# Raspberry_Pi_CM4.net
KiCad netlist of a schematic drawn in Altium Designer
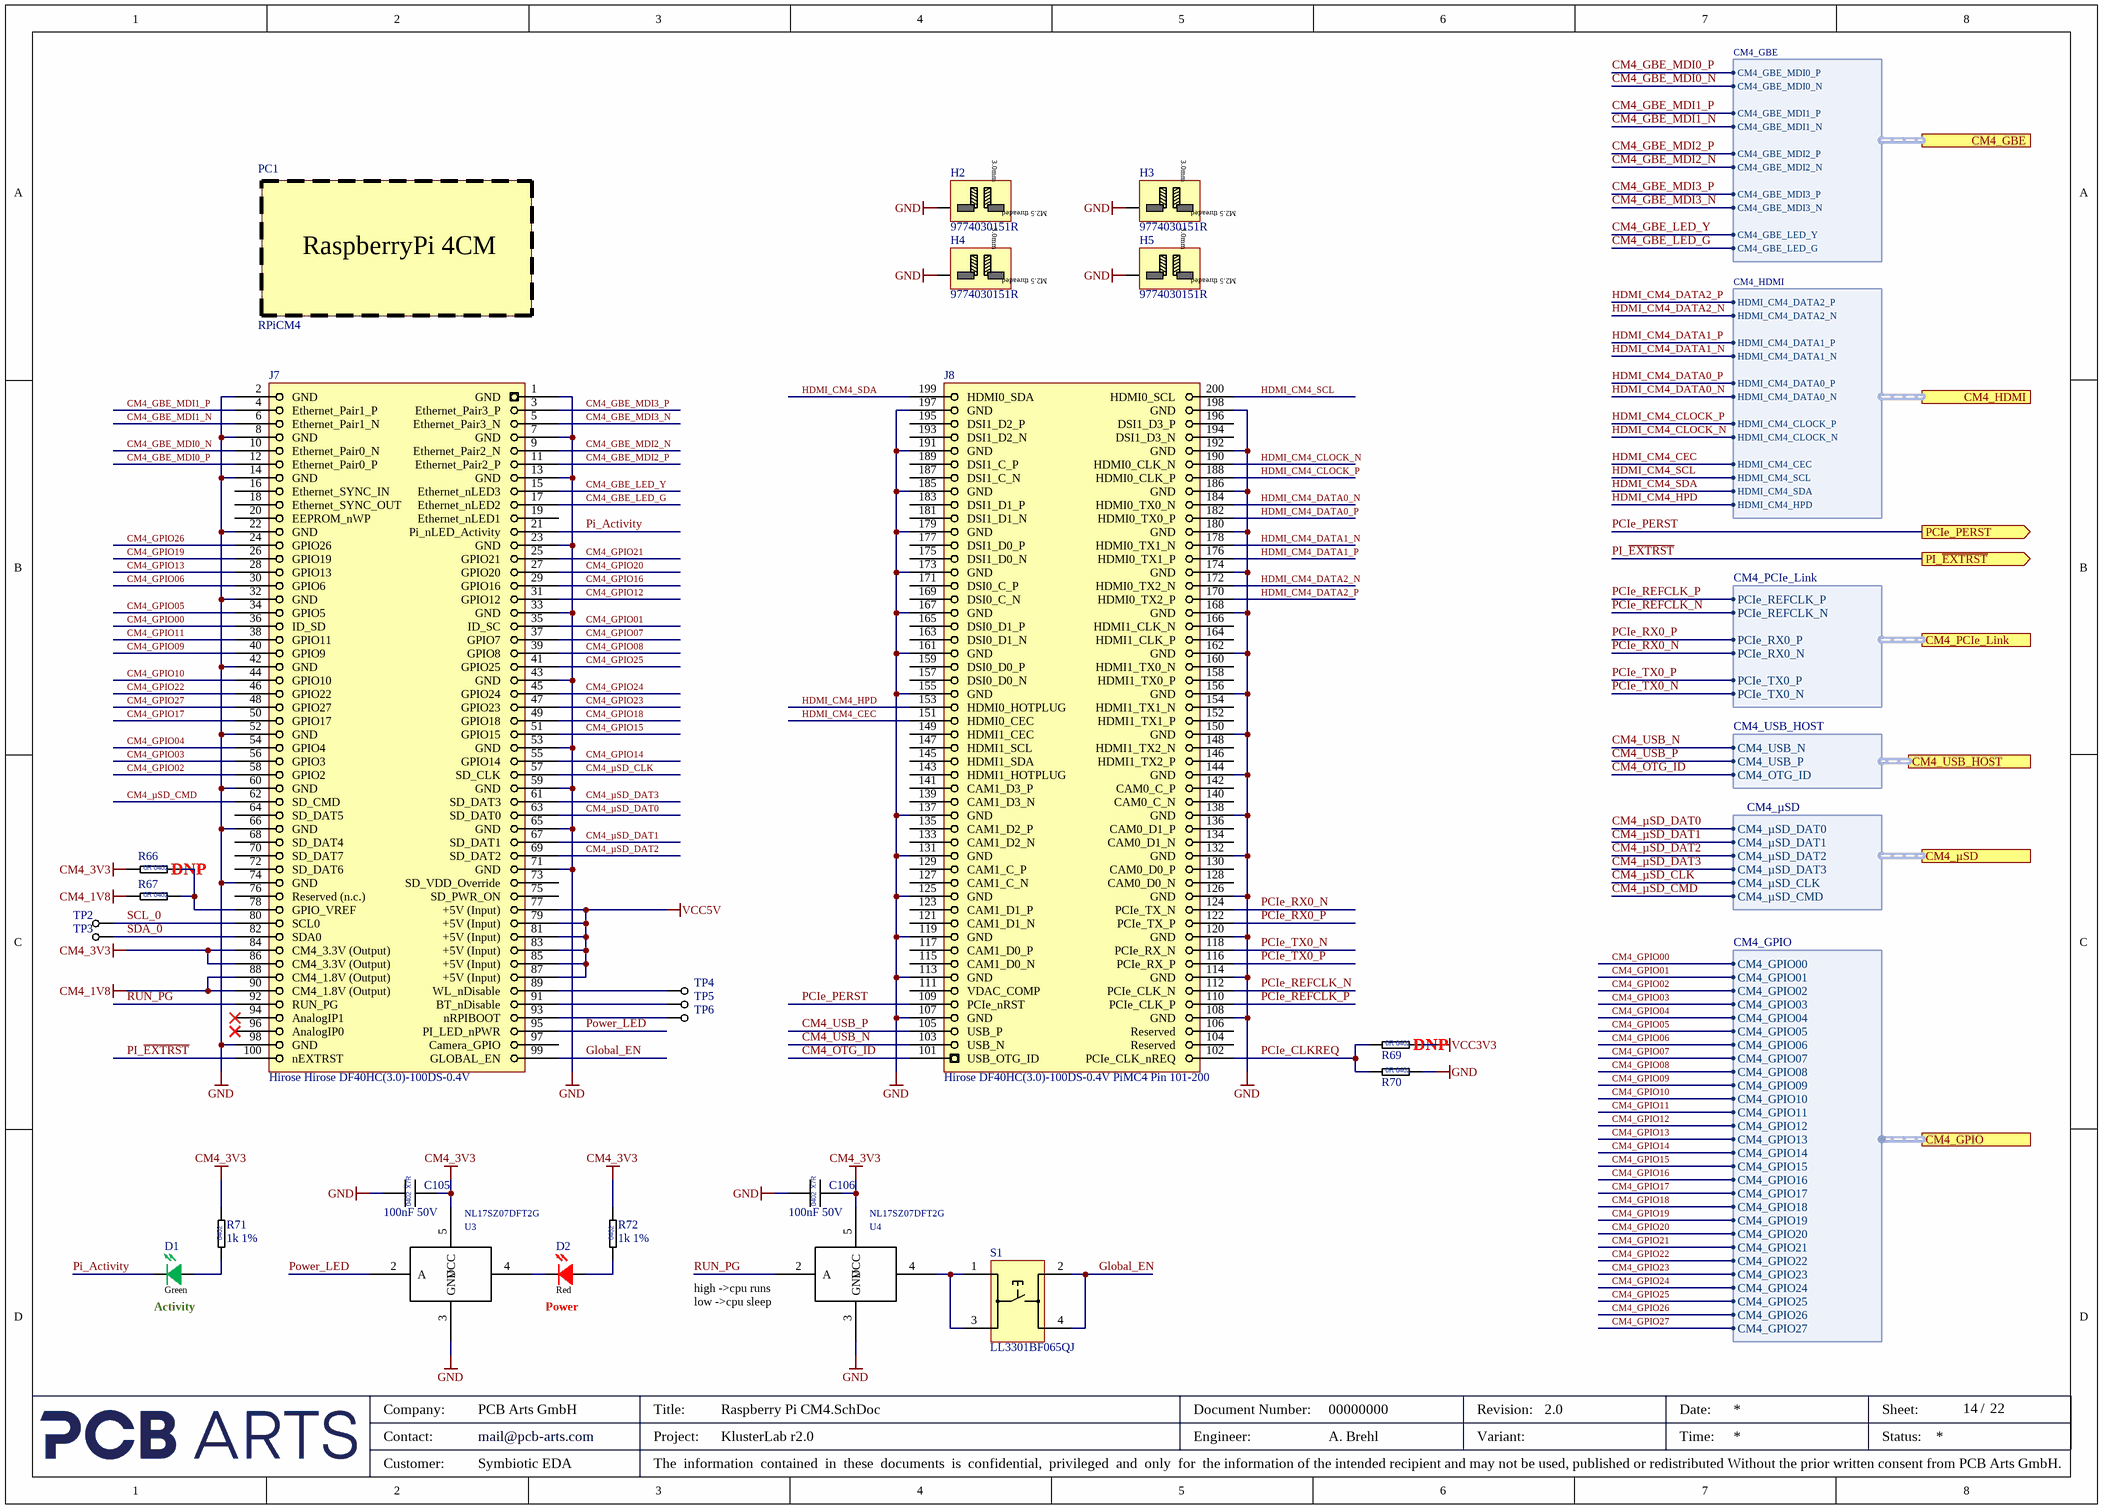
[diagram p0: Raspberry Pi CM4.SchDoc]

(export (version "E")
  (design (tool "Eeschema 10.0.6"))
  (components
    (comp (ref "C105")
      (value "100nF 50V")
      (footprint "Cap:CAP_0402_L")
      (description "Multilayer Ceramic Capacitors MLCC - SMD/SMT 0402 50VDC")
      (libsource (lib "Cap") (part "CAP_0402_100nF_50V"))
    )
    (comp (ref "C106")
      (value "100nF 50V")
      (footprint "Cap:CAP_0402_L")
      (description "Multilayer Ceramic Capacitors MLCC - SMD/SMT 0402 50VDC")
      (libsource (lib "Cap") (part "CAP_0402_100nF_50V"))
    )
    (comp (ref "D1")
      (value "LTST-S270KGKT")
      (footprint "Active:LED-0603 Sideview")
      (description "GREEN  0603 Light Emitting Diode")
      (fields (field (name "COLOR") "Green"))
      (libsource (lib "Active") (part "LED 0603 Green Sideview"))
    )
    (comp (ref "D2")
      (value "LTST-S270KRKT")
      (footprint "Active:LED-0603 Sideview")
      (description "RED  0603 Light Emitting Diode")
      (fields (field (name "COLOR") "Red"))
      (libsource (lib "Active") (part "LED 0603 Red Sideview"))
    )
    (comp (ref "H2")
      (value "9774030151R")
      (footprint "Electro_Mech:9774030151R")
      (description "Würth Standoff M2.5 h:3.0mm 9774030151R")
      (libsource (lib "Electro_Mech") (part "Würth Standoff M2.5 h{colon}3.0mm"))
    )
    (comp (ref "H3")
      (value "9774030151R")
      (footprint "Electro_Mech:9774030151R")
      (description "Würth Standoff M2.5 h:3.0mm 9774030151R")
      (libsource (lib "Electro_Mech") (part "Würth Standoff M2.5 h{colon}3.0mm"))
    )
    (comp (ref "H4")
      (value "9774030151R")
      (footprint "Electro_Mech:9774030151R")
      (description "Würth Standoff M2.5 h:3.0mm 9774030151R")
      (libsource (lib "Electro_Mech") (part "Würth Standoff M2.5 h{colon}3.0mm"))
    )
    (comp (ref "H5")
      (value "9774030151R")
      (footprint "Electro_Mech:9774030151R")
      (description "Würth Standoff M2.5 h:3.0mm 9774030151R")
      (libsource (lib "Electro_Mech") (part "Würth Standoff M2.5 h{colon}3.0mm"))
    )
    (comp (ref "J7")
      (value "Hirose Hirose DF40HC(3.0)-100DS-0.4V")
      (footprint "conn:Hirose DF40HC(3.0)-100DS-0.4V_1-100")
      (description "Hirose DF40HC(3.0)-100DS-0.4V 3mm heigth receptacle for Raspberry Pi CM4, Pin 1-100")
      (libsource (lib "Conn") (part "DF40HC(3.0)-100DS-0.4V RPiCM4 Pin 1-100"))
    )
    (comp (ref "J8")
      (value "Hirose DF40HC(3.0)-100DS-0.4V PiMC4 Pin 101-200")
      (footprint "Conn:Hirose DF40HC(3.0)-100DS-0.4V_101-200")
      (description "Hirose DF40C-100DS-0.4V 3mm heigth receptacle for Raspberry Pi CM4, Pin 101-200")
      (libsource (lib "Conn") (part "DF40HC(3.0)-100DS-0.4V RPiCM4 Pin 101-200"))
    )
    (comp (ref "PC1")
      (value "RPiCM4")
      (footprint "Mechanical:RaspberryPi_CM4")
      (description "Raspberry Pi 4 Compute Module 4")
      (libsource (lib "Mechanical") (part "Raspberry Pi Compute Module 4"))
    )
    (comp (ref "R66")
      (value "0R Jumper")
      (footprint "Res:RES_0402_L")
      (description "Thick Film Resistors - SMD 0Ohm")
      (libsource (lib "Res") (part "RES_0402_0R Jumper"))
    )
    (comp (ref "R67")
      (value "0R Jumper")
      (footprint "Res:RES_0402_L")
      (description "Thick Film Resistors - SMD 0Ohm")
      (libsource (lib "Res") (part "RES_0402_0R Jumper"))
    )
    (comp (ref "R69")
      (value "0R Jumper")
      (footprint "Res:RES_0402_L")
      (description "Thick Film Resistors - SMD 0Ohm")
      (libsource (lib "Res") (part "RES_0402_0R Jumper"))
    )
    (comp (ref "R70")
      (value "0R Jumper")
      (footprint "Res:RES_0402_L")
      (description "Thick Film Resistors - SMD 0Ohm")
      (libsource (lib "Res") (part "RES_0402_0R Jumper"))
    )
    (comp (ref "R71")
      (value "1k 1%")
      (footprint "Res:RES_0402_L")
      (description "Thick Film Resistors - SMD 1kOhm 1%")
      (libsource (lib "Res") (part "RES_0402_1k_1%"))
    )
    (comp (ref "R72")
      (value "1k 1%")
      (footprint "Res:RES_0402_L")
      (description "Thick Film Resistors - SMD 1kOhm 1%")
      (libsource (lib "Res") (part "RES_0402_1k_1%"))
    )
    (comp (ref "S1")
      (value "LL3301BF065QJ")
      (footprint "Electro_Mech:LL3301BF065QJ")
      (description "SPST Top Actuated  Button, 65gf, SMD h: 9.8mm")
      (libsource (lib "Electro_Mech") (part "LL3301BF065QJ_SPST Top Actuated  Button, 65gf, SMD h{colon} 9.8mm"))
    )
    (comp (ref "TP2")
      (value "Testpoint")
      (footprint "Electro_mech:Testpoint 0.8mm")
      (description "Testpoint 0.8mm")
      (libsource (lib "Electro_Mech") (part "Testpoint 0.8mm"))
    )
    (comp (ref "TP3")
      (value "Testpoint")
      (footprint "Electro_mech:Testpoint 0.8mm")
      (description "Testpoint 0.8mm")
      (libsource (lib "Electro_Mech") (part "Testpoint 0.8mm"))
    )
    (comp (ref "TP4")
      (value "Testpoint")
      (footprint "Electro_mech:Testpoint 0.8mm")
      (description "Testpoint 0.8mm")
      (libsource (lib "Electro_Mech") (part "Testpoint 0.8mm"))
    )
    (comp (ref "TP5")
      (value "Testpoint")
      (footprint "Electro_mech:Testpoint 0.8mm")
      (description "Testpoint 0.8mm")
      (libsource (lib "Electro_Mech") (part "Testpoint 0.8mm"))
    )
    (comp (ref "TP6")
      (value "Testpoint")
      (footprint "Electro_mech:Testpoint 0.8mm")
      (description "Testpoint 0.8mm")
      (libsource (lib "Electro_Mech") (part "Testpoint 0.8mm"))
    )
    (comp (ref "U3")
      (value "NL17SZ07DFT2G")
      (footprint "Digital:SOT65P210X110-5N")
      (description "Puffer u. Leitungstreiber 1.65-5.5V Single Non-Inverting")
      (libsource (lib "Digital") (part "NL17SZ07DFT2G_Buffer 1.65-5.5V Single Non-Inverting"))
    )
    (comp (ref "U4")
      (value "NL17SZ07DFT2G")
      (footprint "Digital:SOT65P210X110-5N")
      (description "Puffer u. Leitungstreiber 1.65-5.5V Single Non-Inverting")
      (libsource (lib "Digital") (part "NL17SZ07DFT2G_Buffer 1.65-5.5V Single Non-Inverting"))
    )
  )
  (nets
    (net (code "7") (name "/CM4_GBE_LED_G") (class "Default")
      (node (ref "J7") (pin "17") (pinfunction "Ethernet_nLED2_17") (pintype "passive"))
    )
    (net (code "8") (name "/CM4_GBE_LED_Y") (class "Default")
      (node (ref "J7") (pin "15") (pinfunction "Ethernet_nLED3_15") (pintype "passive"))
    )
    (net (code "9") (name "/CM4_GBE_MDI0_N") (class "Default")
      (node (ref "J7") (pin "10") (pinfunction "Ethernet_Pair0_N_10") (pintype "passive"))
    )
    (net (code "10") (name "/CM4_GBE_MDI0_P") (class "Default")
      (node (ref "J7") (pin "12") (pinfunction "Ethernet_Pair0_P_12") (pintype "passive"))
    )
    (net (code "11") (name "/CM4_GBE_MDI1_N") (class "Default")
      (node (ref "J7") (pin "6") (pinfunction "Ethernet_Pair1_N_6") (pintype "passive"))
    )
    (net (code "12") (name "/CM4_GBE_MDI1_P") (class "Default")
      (node (ref "J7") (pin "4") (pinfunction "Ethernet_Pair1_P_4") (pintype "passive"))
    )
    (net (code "13") (name "/CM4_GBE_MDI2_N") (class "Default")
      (node (ref "J7") (pin "9") (pinfunction "Ethernet_Pair2_N_9") (pintype "passive"))
    )
    (net (code "14") (name "/CM4_GBE_MDI2_P") (class "Default")
      (node (ref "J7") (pin "11") (pinfunction "Ethernet_Pair2_P_11") (pintype "passive"))
    )
    (net (code "15") (name "/CM4_GBE_MDI3_N") (class "Default")
      (node (ref "J7") (pin "5") (pinfunction "Ethernet_Pair3_N_5") (pintype "passive"))
    )
    (net (code "16") (name "/CM4_GBE_MDI3_P") (class "Default")
      (node (ref "J7") (pin "3") (pinfunction "Ethernet_Pair3_P_3") (pintype "passive"))
    )
    (net (code "17") (name "/CM4_GPIO00") (class "Default")
      (node (ref "J7") (pin "36") (pinfunction "ID_SD_36") (pintype "passive"))
    )
    (net (code "18") (name "/CM4_GPIO01") (class "Default")
      (node (ref "J7") (pin "35") (pinfunction "ID_SC_35") (pintype "passive"))
    )
    (net (code "19") (name "/CM4_GPIO02") (class "Default")
      (node (ref "J7") (pin "58") (pinfunction "GPIO2_58") (pintype "passive"))
    )
    (net (code "20") (name "/CM4_GPIO03") (class "Default")
      (node (ref "J7") (pin "56") (pinfunction "GPIO3_56") (pintype "passive"))
    )
    (net (code "21") (name "/CM4_GPIO04") (class "Default")
      (node (ref "J7") (pin "54") (pinfunction "GPIO4_54") (pintype "passive"))
    )
    (net (code "22") (name "/CM4_GPIO05") (class "Default")
      (node (ref "J7") (pin "34") (pinfunction "GPIO5_34") (pintype "passive"))
    )
    (net (code "23") (name "/CM4_GPIO06") (class "Default")
      (node (ref "J7") (pin "30") (pinfunction "GPIO6_30") (pintype "passive"))
    )
    (net (code "24") (name "/CM4_GPIO07") (class "Default")
      (node (ref "J7") (pin "37") (pinfunction "GPIO7_37") (pintype "passive"))
    )
    (net (code "25") (name "/CM4_GPIO08") (class "Default")
      (node (ref "J7") (pin "39") (pinfunction "GPIO8_39") (pintype "passive"))
    )
    (net (code "26") (name "/CM4_GPIO09") (class "Default")
      (node (ref "J7") (pin "40") (pinfunction "GPIO9_40") (pintype "passive"))
    )
    (net (code "27") (name "/CM4_GPIO10") (class "Default")
      (node (ref "J7") (pin "44") (pinfunction "GPIO10_44") (pintype "passive"))
    )
    (net (code "28") (name "/CM4_GPIO11") (class "Default")
      (node (ref "J7") (pin "38") (pinfunction "GPIO11_38") (pintype "passive"))
    )
    (net (code "29") (name "/CM4_GPIO12") (class "Default")
      (node (ref "J7") (pin "31") (pinfunction "GPIO12_31") (pintype "passive"))
    )
    (net (code "30") (name "/CM4_GPIO13") (class "Default")
      (node (ref "J7") (pin "28") (pinfunction "GPIO13_28") (pintype "passive"))
    )
    (net (code "31") (name "/CM4_GPIO14") (class "Default")
      (node (ref "J7") (pin "55") (pinfunction "GPIO14_55") (pintype "passive"))
    )
    (net (code "32") (name "/CM4_GPIO15") (class "Default")
      (node (ref "J7") (pin "51") (pinfunction "GPIO15_51") (pintype "passive"))
    )
    (net (code "33") (name "/CM4_GPIO16") (class "Default")
      (node (ref "J7") (pin "29") (pinfunction "GPIO16_29") (pintype "passive"))
    )
    (net (code "34") (name "/CM4_GPIO17") (class "Default")
      (node (ref "J7") (pin "50") (pinfunction "GPIO17_50") (pintype "passive"))
    )
    (net (code "35") (name "/CM4_GPIO18") (class "Default")
      (node (ref "J7") (pin "49") (pinfunction "GPIO18_49") (pintype "passive"))
    )
    (net (code "36") (name "/CM4_GPIO19") (class "Default")
      (node (ref "J7") (pin "26") (pinfunction "GPIO19_26") (pintype "passive"))
    )
    (net (code "37") (name "/CM4_GPIO20") (class "Default")
      (node (ref "J7") (pin "27") (pinfunction "GPIO20_27") (pintype "passive"))
    )
    (net (code "38") (name "/CM4_GPIO21") (class "Default")
      (node (ref "J7") (pin "25") (pinfunction "GPIO21_25") (pintype "passive"))
    )
    (net (code "39") (name "/CM4_GPIO22") (class "Default")
      (node (ref "J7") (pin "46") (pinfunction "GPIO22_46") (pintype "passive"))
    )
    (net (code "40") (name "/CM4_GPIO23") (class "Default")
      (node (ref "J7") (pin "47") (pinfunction "GPIO23_47") (pintype "passive"))
    )
    (net (code "41") (name "/CM4_GPIO24") (class "Default")
      (node (ref "J7") (pin "45") (pinfunction "GPIO24_45") (pintype "passive"))
    )
    (net (code "42") (name "/CM4_GPIO25") (class "Default")
      (node (ref "J7") (pin "41") (pinfunction "GPIO25_41") (pintype "passive"))
    )
    (net (code "43") (name "/CM4_GPIO26") (class "Default")
      (node (ref "J7") (pin "24") (pinfunction "GPIO26_24") (pintype "passive"))
    )
    (net (code "44") (name "/CM4_GPIO27") (class "Default")
      (node (ref "J7") (pin "48") (pinfunction "GPIO27_48") (pintype "passive"))
    )
    (net (code "45") (name "/CM4_OTG_ID") (class "Default")
      (node (ref "J8") (pin "101") (pinfunction "USB_OTG_ID_101") (pintype "passive"))
    )
    (net (code "46") (name "/CM4_USB_N") (class "Default")
      (node (ref "J8") (pin "103") (pinfunction "USB_N_103") (pintype "passive"))
    )
    (net (code "47") (name "/CM4_USB_P") (class "Default")
      (node (ref "J8") (pin "105") (pinfunction "USB_P_105") (pintype "passive"))
    )
    (net (code "48") (name "/CM4_µSD_CLK") (class "Default")
      (node (ref "J7") (pin "57") (pinfunction "SD_CLK_57") (pintype "passive"))
    )
    (net (code "49") (name "/CM4_µSD_CMD") (class "Default")
      (node (ref "J7") (pin "62") (pinfunction "SD_CMD_62") (pintype "passive"))
    )
    (net (code "50") (name "/CM4_µSD_DAT0") (class "Default")
      (node (ref "J7") (pin "63") (pinfunction "SD_DAT0_63") (pintype "passive"))
    )
    (net (code "51") (name "/CM4_µSD_DAT1") (class "Default")
      (node (ref "J7") (pin "67") (pinfunction "SD_DAT1_67") (pintype "passive"))
    )
    (net (code "52") (name "/CM4_µSD_DAT2") (class "Default")
      (node (ref "J7") (pin "69") (pinfunction "SD_DAT2_69") (pintype "passive"))
    )
    (net (code "53") (name "/CM4_µSD_DAT3") (class "Default")
      (node (ref "J7") (pin "61") (pinfunction "SD_DAT3_61") (pintype "passive"))
    )
    (net (code "54") (name "/Global_EN") (class "Default")
      (node (ref "J7") (pin "99") (pinfunction "GLOBAL_EN_99") (pintype "passive"))
      (node (ref "S1") (pin "2") (pinfunction "2_2") (pintype "passive"))
      (node (ref "S1") (pin "4") (pinfunction "4_4") (pintype "passive"))
    )
    (net (code "55") (name "/HDMI_CM4_CEC") (class "Default")
      (node (ref "J8") (pin "151") (pinfunction "HDMI0_CEC_151") (pintype "passive"))
    )
    (net (code "56") (name "/HDMI_CM4_CLOCK_N") (class "Default")
      (node (ref "J8") (pin "190") (pinfunction "HDMI0_CLK_N_190") (pintype "passive"))
    )
    (net (code "57") (name "/HDMI_CM4_CLOCK_P") (class "Default")
      (node (ref "J8") (pin "188") (pinfunction "HDMI0_CLK_P_188") (pintype "passive"))
    )
    (net (code "58") (name "/HDMI_CM4_DATA0_N") (class "Default")
      (node (ref "J8") (pin "184") (pinfunction "HDMI0_TX0_N_184") (pintype "passive"))
    )
    (net (code "59") (name "/HDMI_CM4_DATA0_P") (class "Default")
      (node (ref "J8") (pin "182") (pinfunction "HDMI0_TX0_P_182") (pintype "passive"))
    )
    (net (code "60") (name "/HDMI_CM4_DATA1_N") (class "Default")
      (node (ref "J8") (pin "178") (pinfunction "HDMI0_TX1_N_178") (pintype "passive"))
    )
    (net (code "61") (name "/HDMI_CM4_DATA1_P") (class "Default")
      (node (ref "J8") (pin "176") (pinfunction "HDMI0_TX1_P_176") (pintype "passive"))
    )
    (net (code "62") (name "/HDMI_CM4_DATA2_N") (class "Default")
      (node (ref "J8") (pin "172") (pinfunction "HDMI0_TX2_N_172") (pintype "passive"))
    )
    (net (code "63") (name "/HDMI_CM4_DATA2_P") (class "Default")
      (node (ref "J8") (pin "170") (pinfunction "HDMI0_TX2_P_170") (pintype "passive"))
    )
    (net (code "64") (name "/HDMI_CM4_HPD") (class "Default")
      (node (ref "J8") (pin "153") (pinfunction "HDMI0_HOTPLUG_153") (pintype "passive"))
    )
    (net (code "65") (name "/HDMI_CM4_SCL") (class "Default")
      (node (ref "J8") (pin "200") (pinfunction "HDMI0_SCL_200") (pintype "passive"))
    )
    (net (code "66") (name "/HDMI_CM4_SDA") (class "Default")
      (node (ref "J8") (pin "199") (pinfunction "HDMI0_SDA_199") (pintype "passive"))
    )
    (net (code "67") (name "/PCIe_CLKREQ") (class "Default")
      (node (ref "J8") (pin "102") (pinfunction "PCIe_CLK_nREQ_102") (pintype "passive"))
      (node (ref "R69") (pin "1") (pinfunction "1_1") (pintype "passive"))
      (node (ref "R70") (pin "1") (pinfunction "1_1") (pintype "passive"))
    )
    (net (code "68") (name "/PCIe_PERST") (class "Default")
      (node (ref "J8") (pin "109") (pinfunction "PCIe_nRST_109") (pintype "passive"))
    )
    (net (code "69") (name "/PCIe_REFCLK_N") (class "Default")
      (node (ref "J8") (pin "112") (pinfunction "PCIe_CLK_N_112") (pintype "passive"))
    )
    (net (code "70") (name "/PCIe_REFCLK_P") (class "Default")
      (node (ref "J8") (pin "110") (pinfunction "PCIe_CLK_P_110") (pintype "passive"))
    )
    (net (code "71") (name "/PCIe_RX0_N") (class "Default")
      (node (ref "J8") (pin "124") (pinfunction "PCIe_TX_N_124") (pintype "passive"))
    )
    (net (code "72") (name "/PCIe_RX0_P") (class "Default")
      (node (ref "J8") (pin "122") (pinfunction "PCIe_TX_P_122") (pintype "passive"))
    )
    (net (code "73") (name "/PCIe_TX0_N") (class "Default")
      (node (ref "J8") (pin "118") (pinfunction "PCIe_RX_N_118") (pintype "passive"))
    )
    (net (code "74") (name "/PCIe_TX0_P") (class "Default")
      (node (ref "J8") (pin "116") (pinfunction "PCIe_RX_P_116") (pintype "passive"))
    )
    (net (code "75") (name "/PI_~{EXTRST}") (class "Default")
      (node (ref "J7") (pin "100") (pinfunction "nEXTRST_100") (pintype "passive"))
    )
    (net (code "76") (name "/Pi_Activity") (class "Default")
      (node (ref "D1") (pin "1") (pinfunction "1_1") (pintype "passive"))
      (node (ref "J7") (pin "21") (pinfunction "Pi_nLED_Activity_21") (pintype "passive"))
    )
    (net (code "77") (name "/Power_LED") (class "Default")
      (node (ref "J7") (pin "95") (pinfunction "PI_LED_nPWR_95") (pintype "passive"))
      (node (ref "U3") (pin "2") (pinfunction "A_2") (pintype "passive"))
    )
    (net (code "78") (name "/RUN_PG") (class "Default")
      (node (ref "J7") (pin "92") (pinfunction "RUN_PG_92") (pintype "passive"))
      (node (ref "U4") (pin "2") (pinfunction "A_2") (pintype "passive"))
    )
    (net (code "79") (name "/SCL_0") (class "Default")
      (node (ref "J7") (pin "80") (pinfunction "SCL0_80") (pintype "passive"))
      (node (ref "TP2") (pin "1") (pinfunction "GND_1") (pintype "passive"))
    )
    (net (code "80") (name "/SDA_0") (class "Default")
      (node (ref "J7") (pin "82") (pinfunction "SDA0_82") (pintype "passive"))
      (node (ref "TP3") (pin "1") (pinfunction "GND_1") (pintype "passive"))
    )
    (net (code "87") (name "CM4_1V8") (class "Default")
      (node (ref "J7") (pin "88") (pinfunction "CM4_1.8V_(Output)_88") (pintype "passive"))
      (node (ref "J7") (pin "90") (pinfunction "CM4_1.8V_(Output)_90") (pintype "passive"))
      (node (ref "R67") (pin "1") (pinfunction "1_1") (pintype "passive"))
    )
    (net (code "88") (name "CM4_3V3") (class "Default")
      (node (ref "C105") (pin "2") (pinfunction "2_2") (pintype "passive"))
      (node (ref "C106") (pin "2") (pinfunction "2_2") (pintype "passive"))
      (node (ref "J7") (pin "84") (pinfunction "CM4_3.3V_(Output)_84") (pintype "passive"))
      (node (ref "J7") (pin "86") (pinfunction "CM4_3.3V_(Output)_86") (pintype "passive"))
      (node (ref "R66") (pin "1") (pinfunction "1_1") (pintype "passive"))
      (node (ref "R71") (pin "2") (pinfunction "2_2") (pintype "passive"))
      (node (ref "R72") (pin "2") (pinfunction "2_2") (pintype "passive"))
      (node (ref "U3") (pin "5") (pinfunction "VCC_5") (pintype "passive"))
      (node (ref "U4") (pin "5") (pinfunction "VCC_5") (pintype "passive"))
    )
    (net (code "89") (name "GND") (class "Default")
      (node (ref "C105") (pin "1") (pinfunction "1_1") (pintype "passive"))
      (node (ref "C106") (pin "1") (pinfunction "1_1") (pintype "passive"))
      (node (ref "H2") (pin "1") (pinfunction "1_1") (pintype "passive"))
      (node (ref "H3") (pin "1") (pinfunction "1_1") (pintype "passive"))
      (node (ref "H4") (pin "1") (pinfunction "1_1") (pintype "passive"))
      (node (ref "H5") (pin "1") (pinfunction "1_1") (pintype "passive"))
      (node (ref "J7") (pin "1") (pinfunction "GND_1") (pintype "passive"))
      (node (ref "J7") (pin "13") (pinfunction "GND_13") (pintype "passive"))
      (node (ref "J7") (pin "14") (pinfunction "GND_14") (pintype "passive"))
      (node (ref "J7") (pin "2") (pinfunction "GND_2") (pintype "passive"))
      (node (ref "J7") (pin "22") (pinfunction "GND_22") (pintype "passive"))
      (node (ref "J7") (pin "23") (pinfunction "GND_23") (pintype "passive"))
      (node (ref "J7") (pin "32") (pinfunction "GND_32") (pintype "passive"))
      (node (ref "J7") (pin "33") (pinfunction "GND_33") (pintype "passive"))
      (node (ref "J7") (pin "42") (pinfunction "GND_42") (pintype "passive"))
      (node (ref "J7") (pin "43") (pinfunction "GND_43") (pintype "passive"))
      (node (ref "J7") (pin "52") (pinfunction "GND_52") (pintype "passive"))
      (node (ref "J7") (pin "53") (pinfunction "GND_53") (pintype "passive"))
      (node (ref "J7") (pin "59") (pinfunction "GND_59") (pintype "passive"))
      (node (ref "J7") (pin "60") (pinfunction "GND_60") (pintype "passive"))
      (node (ref "J7") (pin "65") (pinfunction "GND_65") (pintype "passive"))
      (node (ref "J7") (pin "66") (pinfunction "GND_66") (pintype "passive"))
      (node (ref "J7") (pin "7") (pinfunction "GND_7") (pintype "passive"))
      (node (ref "J7") (pin "71") (pinfunction "GND_71") (pintype "passive"))
      (node (ref "J7") (pin "74") (pinfunction "GND_74") (pintype "passive"))
      (node (ref "J7") (pin "8") (pinfunction "GND_8") (pintype "passive"))
      (node (ref "J7") (pin "98") (pinfunction "GND_98") (pintype "passive"))
      (node (ref "J8") (pin "107") (pinfunction "GND_107") (pintype "passive"))
      (node (ref "J8") (pin "108") (pinfunction "GND_108") (pintype "passive"))
      (node (ref "J8") (pin "113") (pinfunction "GND_113") (pintype "passive"))
      (node (ref "J8") (pin "114") (pinfunction "GND_114") (pintype "passive"))
      (node (ref "J8") (pin "119") (pinfunction "GND_119") (pintype "passive"))
      (node (ref "J8") (pin "120") (pinfunction "GND_120") (pintype "passive"))
      (node (ref "J8") (pin "125") (pinfunction "GND_125") (pintype "passive"))
      (node (ref "J8") (pin "126") (pinfunction "GND_126") (pintype "passive"))
      (node (ref "J8") (pin "131") (pinfunction "GND_131") (pintype "passive"))
      (node (ref "J8") (pin "132") (pinfunction "GND_132") (pintype "passive"))
      (node (ref "J8") (pin "137") (pinfunction "GND_137") (pintype "passive"))
      (node (ref "J8") (pin "138") (pinfunction "GND_138") (pintype "passive"))
      (node (ref "J8") (pin "144") (pinfunction "GND_144") (pintype "passive"))
      (node (ref "J8") (pin "150") (pinfunction "GND_150") (pintype "passive"))
      (node (ref "J8") (pin "155") (pinfunction "GND_155") (pintype "passive"))
      (node (ref "J8") (pin "156") (pinfunction "GND_156") (pintype "passive"))
      (node (ref "J8") (pin "161") (pinfunction "GND_161") (pintype "passive"))
      (node (ref "J8") (pin "162") (pinfunction "GND_162") (pintype "passive"))
      (node (ref "J8") (pin "167") (pinfunction "GND_167") (pintype "passive"))
      (node (ref "J8") (pin "168") (pinfunction "GND_168") (pintype "passive"))
      (node (ref "J8") (pin "173") (pinfunction "GND_173") (pintype "passive"))
      (node (ref "J8") (pin "174") (pinfunction "GND_174") (pintype "passive"))
      (node (ref "J8") (pin "179") (pinfunction "GND_179") (pintype "passive"))
      (node (ref "J8") (pin "180") (pinfunction "GND_180") (pintype "passive"))
      (node (ref "J8") (pin "185") (pinfunction "GND_185") (pintype "passive"))
      (node (ref "J8") (pin "186") (pinfunction "GND_186") (pintype "passive"))
      (node (ref "J8") (pin "191") (pinfunction "GND_191") (pintype "passive"))
      (node (ref "J8") (pin "192") (pinfunction "GND_192") (pintype "passive"))
      (node (ref "J8") (pin "197") (pinfunction "GND_197") (pintype "passive"))
      (node (ref "J8") (pin "198") (pinfunction "GND_198") (pintype "passive"))
      (node (ref "R70") (pin "2") (pinfunction "2_2") (pintype "passive"))
      (node (ref "U3") (pin "3") (pinfunction "GND_3") (pintype "passive"))
      (node (ref "U4") (pin "3") (pinfunction "GND_3") (pintype "passive"))
    )
    (net (code "90") (name "Net-(D1-Pad2)") (class "Default")
      (node (ref "D1") (pin "2") (pinfunction "2_2") (pintype "passive"))
      (node (ref "R71") (pin "1") (pinfunction "1_1") (pintype "passive"))
    )
    (net (code "91") (name "Net-(D2-Pad2)") (class "Default")
      (node (ref "D2") (pin "2") (pinfunction "2_2") (pintype "passive"))
      (node (ref "R72") (pin "1") (pinfunction "1_1") (pintype "passive"))
    )
    (net (code "92") (name "Net-(J7-BT_nDisable)") (class "Default")
      (node (ref "J7") (pin "91") (pinfunction "BT_nDisable_91") (pintype "passive"))
      (node (ref "TP5") (pin "1") (pinfunction "GND_1") (pintype "passive"))
    )
    (net (code "93") (name "Net-(J7-GPIO_VREF)") (class "Default")
      (node (ref "J7") (pin "78") (pinfunction "GPIO_VREF_78") (pintype "passive"))
      (node (ref "R66") (pin "2") (pinfunction "2_2") (pintype "passive"))
      (node (ref "R67") (pin "2") (pinfunction "2_2") (pintype "passive"))
    )
    (net (code "94") (name "Net-(J7-WL_nDisable)") (class "Default")
      (node (ref "J7") (pin "89") (pinfunction "WL_nDisable_89") (pintype "passive"))
      (node (ref "TP4") (pin "1") (pinfunction "GND_1") (pintype "passive"))
    )
    (net (code "95") (name "Net-(J7-nRPIBOOT)") (class "Default")
      (node (ref "J7") (pin "93") (pinfunction "nRPIBOOT_93") (pintype "passive"))
      (node (ref "TP6") (pin "1") (pinfunction "GND_1") (pintype "passive"))
    )
    (net (code "96") (name "Net-(U3-Y)") (class "Default")
      (node (ref "D2") (pin "1") (pinfunction "1_1") (pintype "passive"))
      (node (ref "U3") (pin "4") (pinfunction "Y_4") (pintype "passive"))
    )
    (net (code "97") (name "Net-(U4-Y)") (class "Default")
      (node (ref "S1") (pin "1") (pinfunction "1_1") (pintype "passive"))
      (node (ref "S1") (pin "3") (pinfunction "3_3") (pintype "passive"))
      (node (ref "U4") (pin "4") (pinfunction "Y_4") (pintype "passive"))
    )
    (net (code "98") (name "VCC3V3") (class "Default")
      (node (ref "R69") (pin "2") (pinfunction "2_2") (pintype "passive"))
    )
    (net (code "99") (name "VCC5V") (class "Default")
      (node (ref "J7") (pin "77") (pinfunction "+5V_(Input)_77") (pintype "passive"))
      (node (ref "J7") (pin "79") (pinfunction "+5V_(Input)_79") (pintype "passive"))
      (node (ref "J7") (pin "81") (pinfunction "+5V_(Input)_81") (pintype "passive"))
      (node (ref "J7") (pin "83") (pinfunction "+5V_(Input)_83") (pintype "passive"))
      (node (ref "J7") (pin "85") (pinfunction "+5V_(Input)_85") (pintype "passive"))
      (node (ref "J7") (pin "87") (pinfunction "+5V_(Input)_87") (pintype "passive"))
    )
    (net (code "100") (name "unconnected-(J7-AnalogIP0-Pad96)") (class "Default")
      (node (ref "J7") (pin "96") (pinfunction "AnalogIP0_96") (pintype "passive+no_connect"))
    )
    (net (code "101") (name "unconnected-(J7-AnalogIP1-Pad94)") (class "Default")
      (node (ref "J7") (pin "94") (pinfunction "AnalogIP1_94") (pintype "passive+no_connect"))
    )
    (net (code "102") (name "unconnected-(J7-Camera_GPIO-Pad97)") (class "Default")
      (node (ref "J7") (pin "97") (pinfunction "Camera_GPIO_97") (pintype "passive"))
    )
    (net (code "103") (name "unconnected-(J7-EEPROM_nWP-Pad20)") (class "Default")
      (node (ref "J7") (pin "20") (pinfunction "EEPROM_nWP_20") (pintype "passive"))
    )
    (net (code "104") (name "unconnected-(J7-Ethernet_SYNC_IN-Pad16)") (class "Default")
      (node (ref "J7") (pin "16") (pinfunction "Ethernet_SYNC_IN_16") (pintype "passive"))
    )
    (net (code "105") (name "unconnected-(J7-Ethernet_SYNC_OUT-Pad18)") (class "Default")
      (node (ref "J7") (pin "18") (pinfunction "Ethernet_SYNC_OUT_18") (pintype "passive"))
    )
    (net (code "106") (name "unconnected-(J7-Ethernet_nLED1-Pad19)") (class "Default")
      (node (ref "J7") (pin "19") (pinfunction "Ethernet_nLED1_19") (pintype "passive"))
    )
    (net (code "107") (name "unconnected-(J7-Reserved_(n.c.)-Pad76)") (class "Default")
      (node (ref "J7") (pin "76") (pinfunction "Reserved_(n.c.)_76") (pintype "passive"))
    )
    (net (code "108") (name "unconnected-(J7-SD_DAT4-Pad68)") (class "Default")
      (node (ref "J7") (pin "68") (pinfunction "SD_DAT4_68") (pintype "passive"))
    )
    (net (code "109") (name "unconnected-(J7-SD_DAT5-Pad64)") (class "Default")
      (node (ref "J7") (pin "64") (pinfunction "SD_DAT5_64") (pintype "passive"))
    )
    (net (code "110") (name "unconnected-(J7-SD_DAT6-Pad72)") (class "Default")
      (node (ref "J7") (pin "72") (pinfunction "SD_DAT6_72") (pintype "passive"))
    )
    (net (code "111") (name "unconnected-(J7-SD_DAT7-Pad70)") (class "Default")
      (node (ref "J7") (pin "70") (pinfunction "SD_DAT7_70") (pintype "passive"))
    )
    (net (code "112") (name "unconnected-(J7-SD_PWR_ON-Pad75)") (class "Default")
      (node (ref "J7") (pin "75") (pinfunction "SD_PWR_ON_75") (pintype "passive"))
    )
    (net (code "113") (name "unconnected-(J7-SD_VDD_Override-Pad73)") (class "Default")
      (node (ref "J7") (pin "73") (pinfunction "SD_VDD_Override_73") (pintype "passive"))
    )
    (net (code "114") (name "unconnected-(J8-CAM0_C_N-Pad140)") (class "Default")
      (node (ref "J8") (pin "140") (pinfunction "CAM0_C_N_140") (pintype "passive"))
    )
    (net (code "115") (name "unconnected-(J8-CAM0_C_P-Pad142)") (class "Default")
      (node (ref "J8") (pin "142") (pinfunction "CAM0_C_P_142") (pintype "passive"))
    )
    (net (code "116") (name "unconnected-(J8-CAM0_D0_N-Pad128)") (class "Default")
      (node (ref "J8") (pin "128") (pinfunction "CAM0_D0_N_128") (pintype "passive"))
    )
    (net (code "117") (name "unconnected-(J8-CAM0_D0_P-Pad130)") (class "Default")
      (node (ref "J8") (pin "130") (pinfunction "CAM0_D0_P_130") (pintype "passive"))
    )
    (net (code "118") (name "unconnected-(J8-CAM0_D1_N-Pad134)") (class "Default")
      (node (ref "J8") (pin "134") (pinfunction "CAM0_D1_N_134") (pintype "passive"))
    )
    (net (code "119") (name "unconnected-(J8-CAM0_D1_P-Pad136)") (class "Default")
      (node (ref "J8") (pin "136") (pinfunction "CAM0_D1_P_136") (pintype "passive"))
    )
    (net (code "120") (name "unconnected-(J8-CAM1_C_N-Pad127)") (class "Default")
      (node (ref "J8") (pin "127") (pinfunction "CAM1_C_N_127") (pintype "passive"))
    )
    (net (code "121") (name "unconnected-(J8-CAM1_C_P-Pad129)") (class "Default")
      (node (ref "J8") (pin "129") (pinfunction "CAM1_C_P_129") (pintype "passive"))
    )
    (net (code "122") (name "unconnected-(J8-CAM1_D0_N-Pad115)") (class "Default")
      (node (ref "J8") (pin "115") (pinfunction "CAM1_D0_N_115") (pintype "passive"))
    )
    (net (code "123") (name "unconnected-(J8-CAM1_D0_P-Pad117)") (class "Default")
      (node (ref "J8") (pin "117") (pinfunction "CAM1_D0_P_117") (pintype "passive"))
    )
    (net (code "124") (name "unconnected-(J8-CAM1_D1_N-Pad121)") (class "Default")
      (node (ref "J8") (pin "121") (pinfunction "CAM1_D1_N_121") (pintype "passive"))
    )
    (net (code "125") (name "unconnected-(J8-CAM1_D1_P-Pad123)") (class "Default")
      (node (ref "J8") (pin "123") (pinfunction "CAM1_D1_P_123") (pintype "passive"))
    )
    (net (code "126") (name "unconnected-(J8-CAM1_D2_N-Pad133)") (class "Default")
      (node (ref "J8") (pin "133") (pinfunction "CAM1_D2_N_133") (pintype "passive"))
    )
    (net (code "127") (name "unconnected-(J8-CAM1_D2_P-Pad135)") (class "Default")
      (node (ref "J8") (pin "135") (pinfunction "CAM1_D2_P_135") (pintype "passive"))
    )
    (net (code "128") (name "unconnected-(J8-CAM1_D3_N-Pad139)") (class "Default")
      (node (ref "J8") (pin "139") (pinfunction "CAM1_D3_N_139") (pintype "passive"))
    )
    (net (code "129") (name "unconnected-(J8-CAM1_D3_P-Pad141)") (class "Default")
      (node (ref "J8") (pin "141") (pinfunction "CAM1_D3_P_141") (pintype "passive"))
    )
    (net (code "130") (name "unconnected-(J8-DSI0_C_N-Pad169)") (class "Default")
      (node (ref "J8") (pin "169") (pinfunction "DSI0_C_N_169") (pintype "passive"))
    )
    (net (code "131") (name "unconnected-(J8-DSI0_C_P-Pad171)") (class "Default")
      (node (ref "J8") (pin "171") (pinfunction "DSI0_C_P_171") (pintype "passive"))
    )
    (net (code "132") (name "unconnected-(J8-DSI0_D0_N-Pad157)") (class "Default")
      (node (ref "J8") (pin "157") (pinfunction "DSI0_D0_N_157") (pintype "passive"))
    )
    (net (code "133") (name "unconnected-(J8-DSI0_D0_P-Pad159)") (class "Default")
      (node (ref "J8") (pin "159") (pinfunction "DSI0_D0_P_159") (pintype "passive"))
    )
    (net (code "134") (name "unconnected-(J8-DSI0_D1_N-Pad163)") (class "Default")
      (node (ref "J8") (pin "163") (pinfunction "DSI0_D1_N_163") (pintype "passive"))
    )
    (net (code "135") (name "unconnected-(J8-DSI0_D1_P-Pad165)") (class "Default")
      (node (ref "J8") (pin "165") (pinfunction "DSI0_D1_P_165") (pintype "passive"))
    )
    (net (code "136") (name "unconnected-(J8-DSI1_C_N-Pad187)") (class "Default")
      (node (ref "J8") (pin "187") (pinfunction "DSI1_C_N_187") (pintype "passive"))
    )
    (net (code "137") (name "unconnected-(J8-DSI1_C_P-Pad189)") (class "Default")
      (node (ref "J8") (pin "189") (pinfunction "DSI1_C_P_189") (pintype "passive"))
    )
    (net (code "138") (name "unconnected-(J8-DSI1_D0_N-Pad175)") (class "Default")
      (node (ref "J8") (pin "175") (pinfunction "DSI1_D0_N_175") (pintype "passive"))
    )
    (net (code "139") (name "unconnected-(J8-DSI1_D0_P-Pad177)") (class "Default")
      (node (ref "J8") (pin "177") (pinfunction "DSI1_D0_P_177") (pintype "passive"))
    )
    (net (code "140") (name "unconnected-(J8-DSI1_D1_N-Pad181)") (class "Default")
      (node (ref "J8") (pin "181") (pinfunction "DSI1_D1_N_181") (pintype "passive"))
    )
    (net (code "141") (name "unconnected-(J8-DSI1_D1_P-Pad183)") (class "Default")
      (node (ref "J8") (pin "183") (pinfunction "DSI1_D1_P_183") (pintype "passive"))
    )
    (net (code "142") (name "unconnected-(J8-DSI1_D2_N-Pad193)") (class "Default")
      (node (ref "J8") (pin "193") (pinfunction "DSI1_D2_N_193") (pintype "passive"))
    )
    (net (code "143") (name "unconnected-(J8-DSI1_D2_P-Pad195)") (class "Default")
      (node (ref "J8") (pin "195") (pinfunction "DSI1_D2_P_195") (pintype "passive"))
    )
    (net (code "144") (name "unconnected-(J8-DSI1_D3_N-Pad194)") (class "Default")
      (node (ref "J8") (pin "194") (pinfunction "DSI1_D3_N_194") (pintype "passive"))
    )
    (net (code "145") (name "unconnected-(J8-DSI1_D3_P-Pad196)") (class "Default")
      (node (ref "J8") (pin "196") (pinfunction "DSI1_D3_P_196") (pintype "passive"))
    )
    (net (code "146") (name "unconnected-(J8-HDMI1_CEC-Pad149)") (class "Default")
      (node (ref "J8") (pin "149") (pinfunction "HDMI1_CEC_149") (pintype "passive"))
    )
    (net (code "147") (name "unconnected-(J8-HDMI1_CLK_N-Pad166)") (class "Default")
      (node (ref "J8") (pin "166") (pinfunction "HDMI1_CLK_N_166") (pintype "passive"))
    )
    (net (code "148") (name "unconnected-(J8-HDMI1_CLK_P-Pad164)") (class "Default")
      (node (ref "J8") (pin "164") (pinfunction "HDMI1_CLK_P_164") (pintype "passive"))
    )
    (net (code "149") (name "unconnected-(J8-HDMI1_HOTPLUG-Pad143)") (class "Default")
      (node (ref "J8") (pin "143") (pinfunction "HDMI1_HOTPLUG_143") (pintype "passive"))
    )
    (net (code "150") (name "unconnected-(J8-HDMI1_SCL-Pad147)") (class "Default")
      (node (ref "J8") (pin "147") (pinfunction "HDMI1_SCL_147") (pintype "passive"))
    )
    (net (code "151") (name "unconnected-(J8-HDMI1_SDA-Pad145)") (class "Default")
      (node (ref "J8") (pin "145") (pinfunction "HDMI1_SDA_145") (pintype "passive"))
    )
    (net (code "152") (name "unconnected-(J8-HDMI1_TX0_N-Pad160)") (class "Default")
      (node (ref "J8") (pin "160") (pinfunction "HDMI1_TX0_N_160") (pintype "passive"))
    )
    (net (code "153") (name "unconnected-(J8-HDMI1_TX0_P-Pad158)") (class "Default")
      (node (ref "J8") (pin "158") (pinfunction "HDMI1_TX0_P_158") (pintype "passive"))
    )
    (net (code "154") (name "unconnected-(J8-HDMI1_TX1_N-Pad154)") (class "Default")
      (node (ref "J8") (pin "154") (pinfunction "HDMI1_TX1_N_154") (pintype "passive"))
    )
    (net (code "155") (name "unconnected-(J8-HDMI1_TX1_P-Pad152)") (class "Default")
      (node (ref "J8") (pin "152") (pinfunction "HDMI1_TX1_P_152") (pintype "passive"))
    )
    (net (code "156") (name "unconnected-(J8-HDMI1_TX2_N-Pad148)") (class "Default")
      (node (ref "J8") (pin "148") (pinfunction "HDMI1_TX2_N_148") (pintype "passive"))
    )
    (net (code "157") (name "unconnected-(J8-HDMI1_TX2_P-Pad146)") (class "Default")
      (node (ref "J8") (pin "146") (pinfunction "HDMI1_TX2_P_146") (pintype "passive"))
    )
    (net (code "158") (name "unconnected-(J8-Reserved-Pad104)") (class "Default")
      (node (ref "J8") (pin "104") (pinfunction "Reserved_104") (pintype "passive"))
    )
    (net (code "159") (name "unconnected-(J8-Reserved-Pad106)") (class "Default")
      (node (ref "J8") (pin "106") (pinfunction "Reserved_106") (pintype "passive"))
    )
    (net (code "160") (name "unconnected-(J8-VDAC_COMP-Pad111)") (class "Default")
      (node (ref "J8") (pin "111") (pinfunction "VDAC_COMP_111") (pintype "passive"))
    )
  )
)
